# moister-v1_0.net
KiCad netlist of a schematic drawn in EAGLE
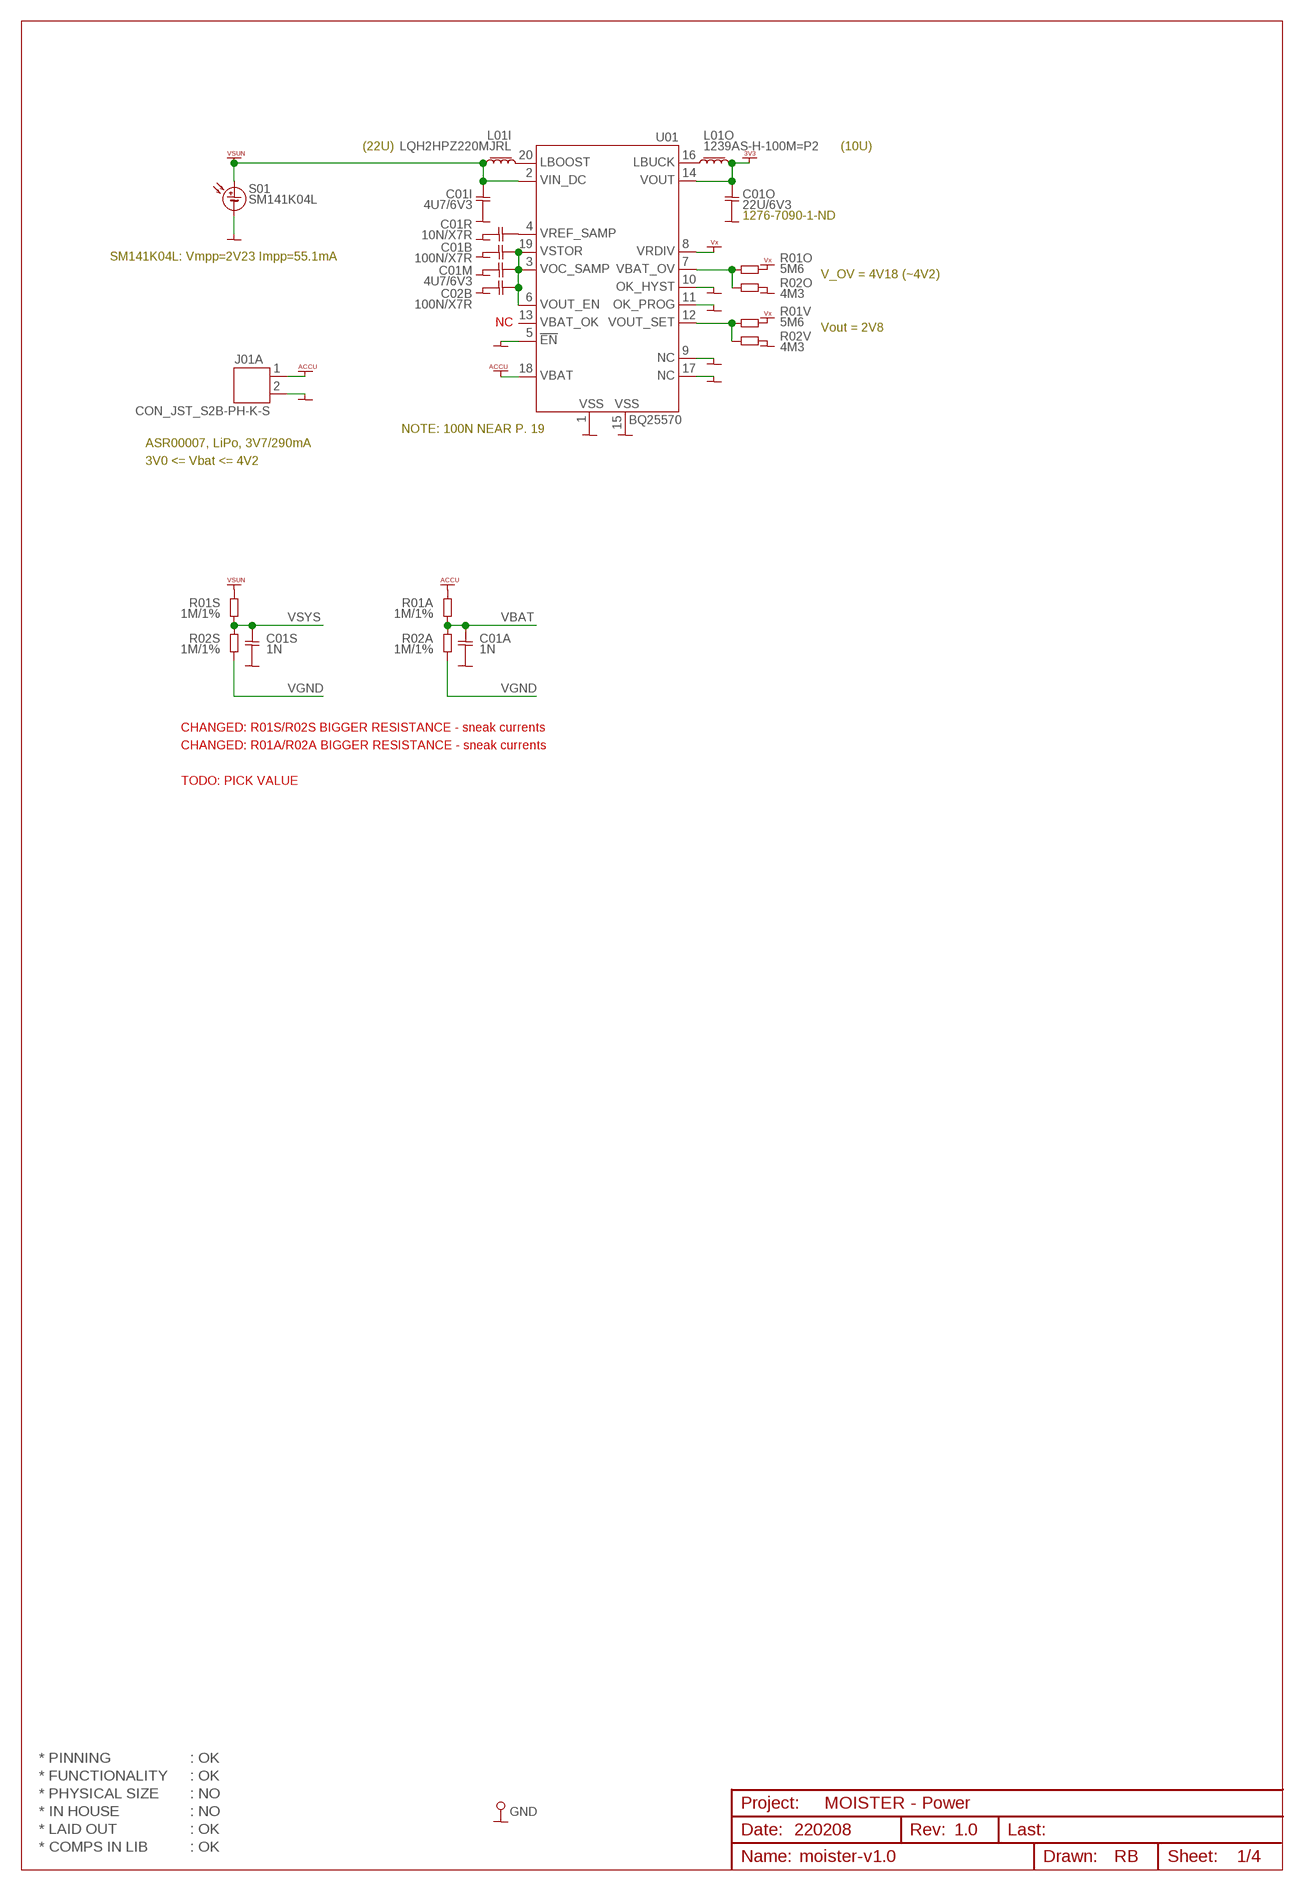
[diagram p0: schematic, sheet 1]
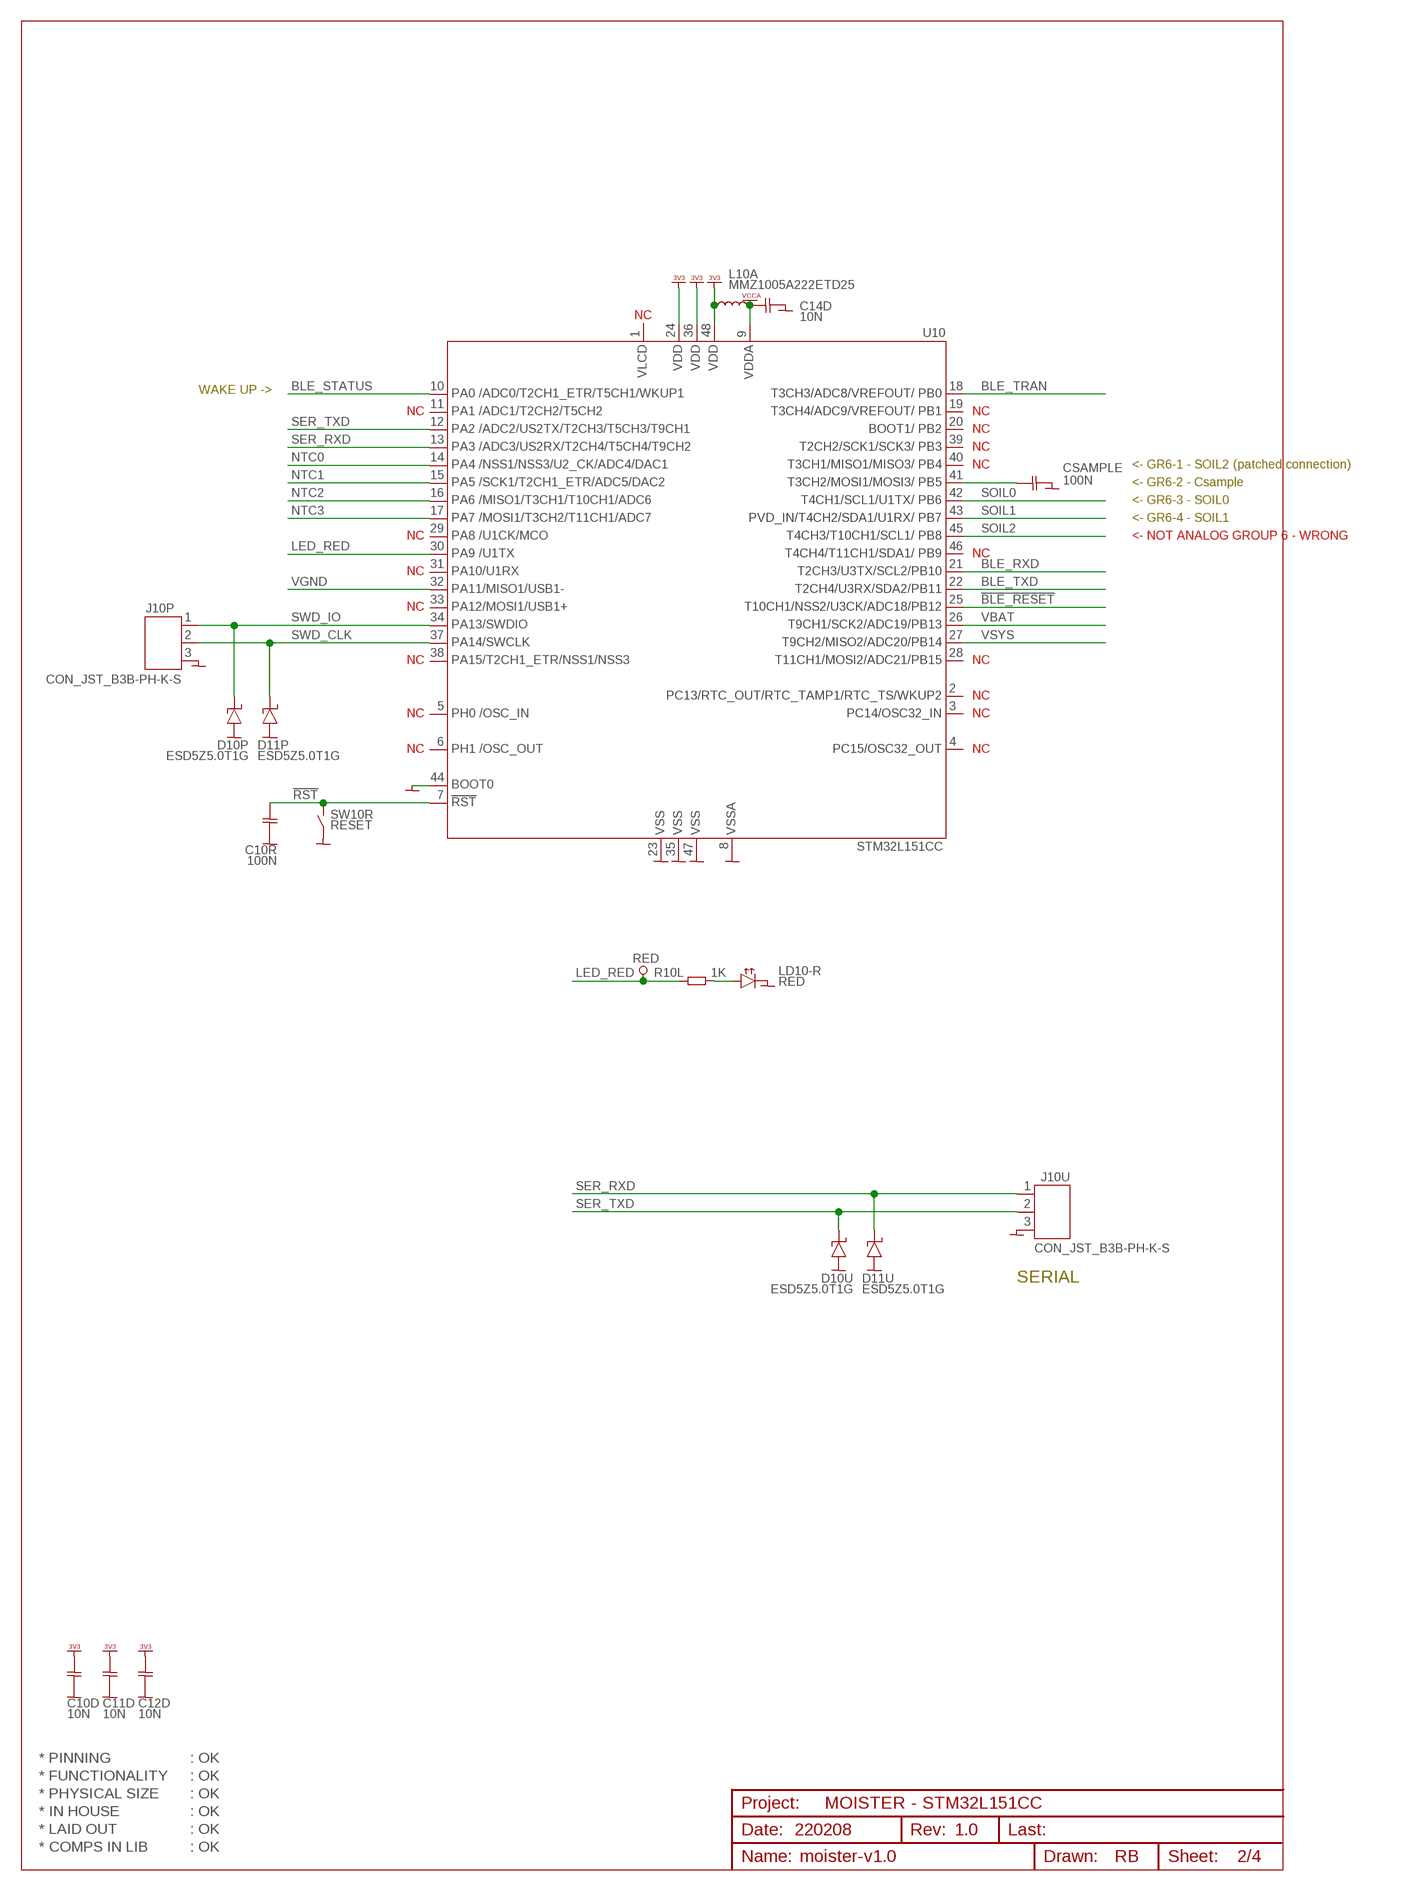
[diagram p1: schematic, sheet 2]
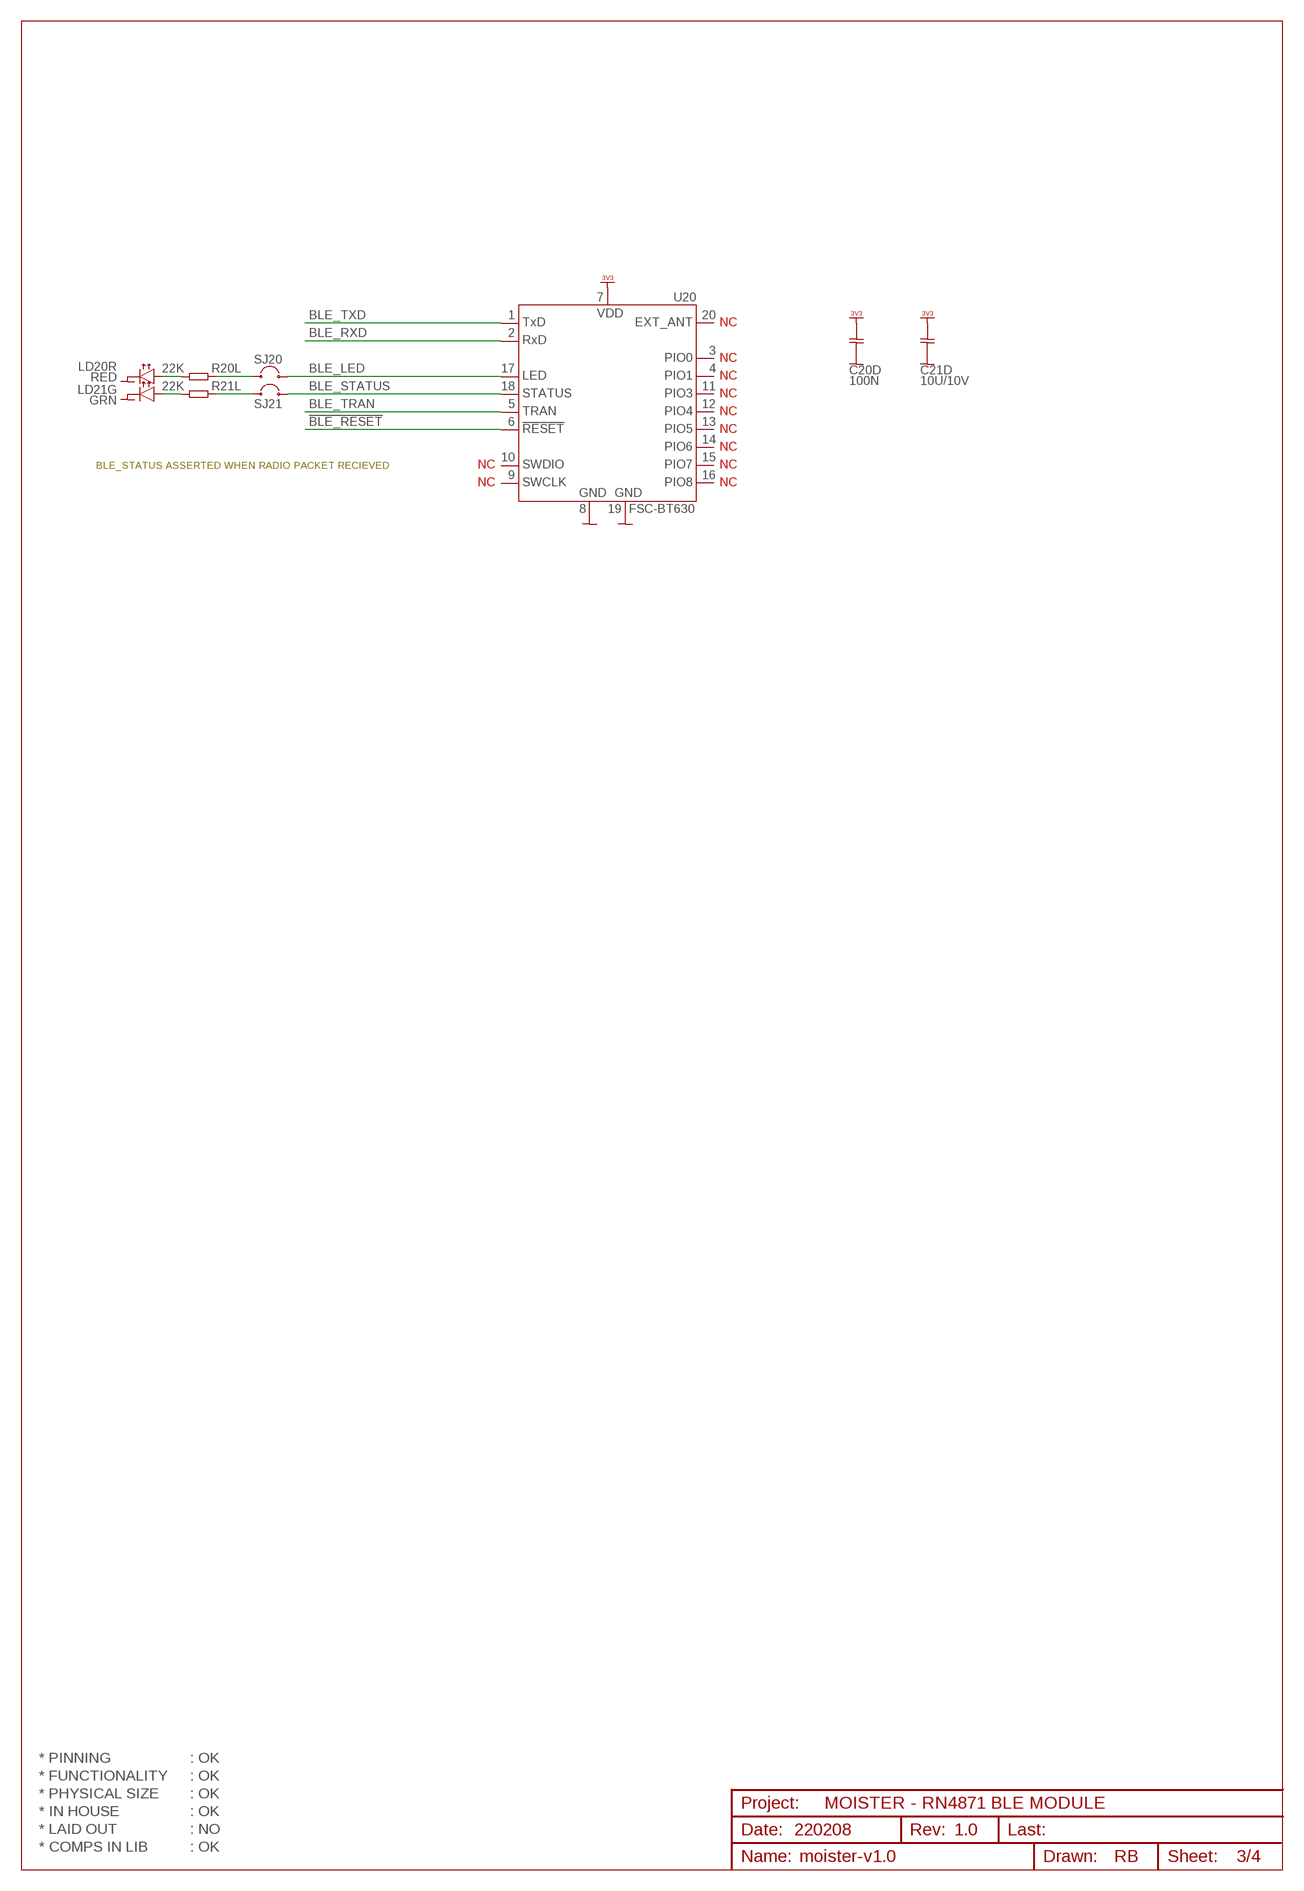
[diagram p2: schematic, sheet 3]
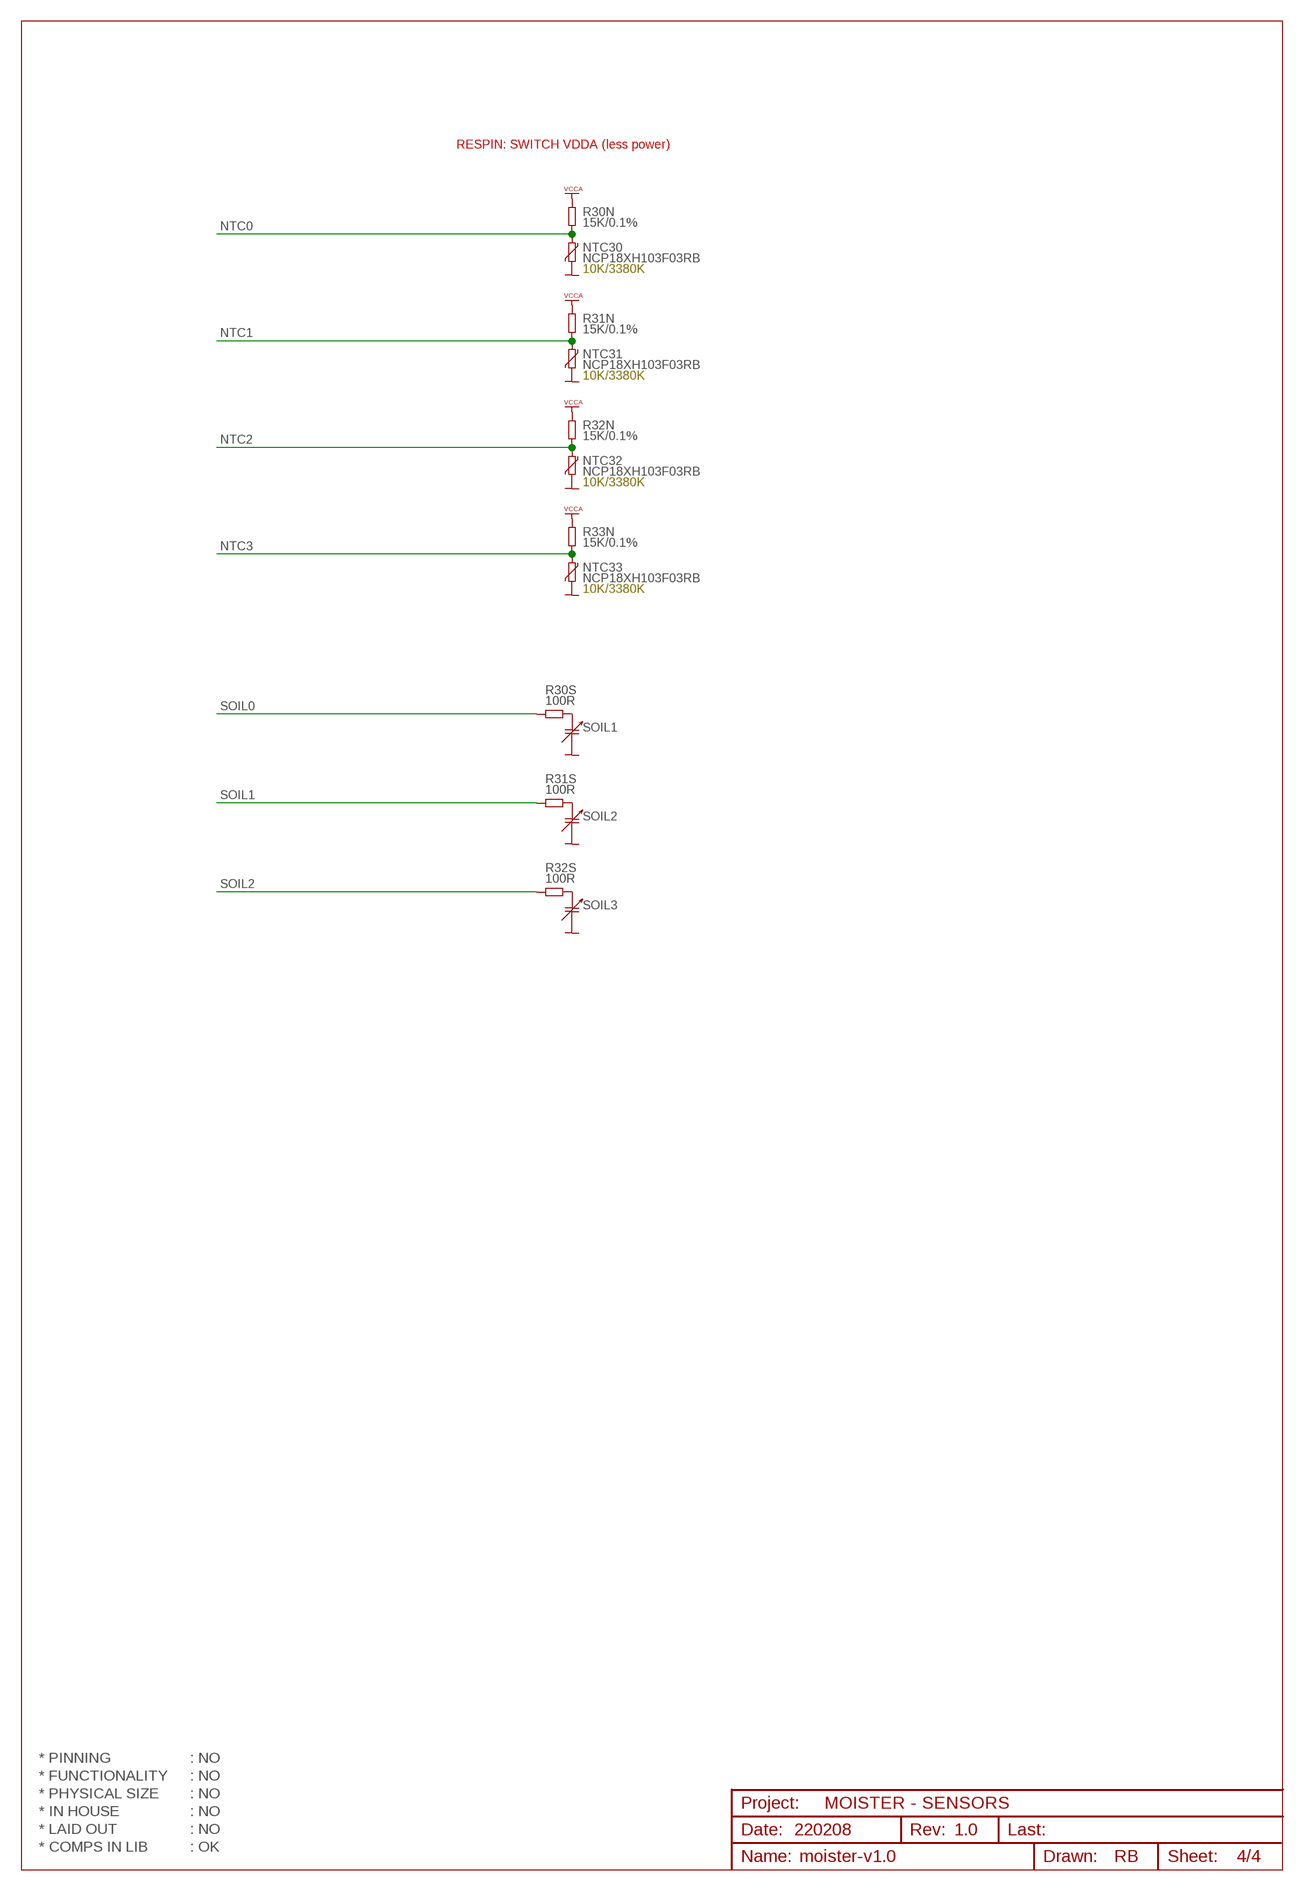
[diagram p3: schematic, sheet 4]

(export (version "E")
  (design (tool "Eeschema 10.0.6"))
  (components
    (comp (ref "C10D")
      (value "10N")
      (footprint "eagle-import:CAP0402")
      (libsource (lib "eagle-import") (part "CAP0402"))
    )
    (comp (ref "C10R")
      (value "100N")
      (footprint "eagle-import:CAP0402")
      (libsource (lib "eagle-import") (part "CAP0402"))
    )
    (comp (ref "C11D")
      (value "10N")
      (footprint "eagle-import:CAP0402")
      (libsource (lib "eagle-import") (part "CAP0402"))
    )
    (comp (ref "C12D")
      (value "10N")
      (footprint "eagle-import:CAP0402")
      (libsource (lib "eagle-import") (part "CAP0402"))
    )
    (comp (ref "C14D")
      (value "10N")
      (footprint "eagle-import:CAP0402")
      (libsource (lib "eagle-import") (part "CAP0402"))
    )
    (comp (ref "CSAMPLE")
      (value "100N")
      (footprint "eagle-import:CAP0603")
      (libsource (lib "eagle-import") (part "CAP0603"))
    )
    (comp (ref "D10P")
      (value "ESD5Z5.0T1G")
      (footprint "eagle-import:DIODE_SOD523")
      (libsource (lib "eagle-import") (part "DIODE_TVS_SOD523"))
    )
    (comp (ref "D10U")
      (value "ESD5Z5.0T1G")
      (footprint "eagle-import:DIODE_SOD523")
      (libsource (lib "eagle-import") (part "DIODE_TVS_SOD523"))
    )
    (comp (ref "D11P")
      (value "ESD5Z5.0T1G")
      (footprint "eagle-import:DIODE_SOD523")
      (libsource (lib "eagle-import") (part "DIODE_TVS_SOD523"))
    )
    (comp (ref "D11U")
      (value "ESD5Z5.0T1G")
      (footprint "eagle-import:DIODE_SOD523")
      (libsource (lib "eagle-import") (part "DIODE_TVS_SOD523"))
    )
    (comp (ref "J10P")
      (value "CON_JST_B3B-PH-K-S")
      (footprint "eagle-import:CON_JST_B3B-PH-K-S")
      (libsource (lib "eagle-import") (part "CON_JST_B3B-PH-K-S"))
    )
    (comp (ref "J10U")
      (value "CON_JST_B3B-PH-K-S")
      (footprint "eagle-import:CON_JST_B3B-PH-K-S")
      (libsource (lib "eagle-import") (part "CON_JST_B3B-PH-K-S"))
    )
    (comp (ref "L10A")
      (value "MMZ1005A222ETD25")
      (footprint "eagle-import:L_0402")
      (libsource (lib "eagle-import") (part "L_0402"))
    )
    (comp (ref "LD10-R")
      (value "RED")
      (footprint "eagle-import:LED_SMD_0402")
      (libsource (lib "eagle-import") (part "LED_SMD_0402"))
    )
    (comp (ref "R10L")
      (value "1K")
      (footprint "eagle-import:RES0402")
      (libsource (lib "eagle-import") (part "RES0402"))
    )
    (comp (ref "RED")
      (value "PIN_TEST_0.6MM")
      (footprint "eagle-import:HOLE_PTH_0.6MM")
      (libsource (lib "eagle-import") (part "PIN_TEST_0.6MM"))
    )
    (comp (ref "SW10R")
      (value "RESET")
      (footprint "eagle-import:SWITCH_SMD_PBUTTON_2P")
      (libsource (lib "eagle-import") (part "SWITCH_PUSHBUTTON"))
    )
    (comp (ref "U10")
      (value "STM32L151CC")
      (footprint "eagle-import:LQFP48")
      (libsource (lib "eagle-import") (part "STM32L151CC"))
    )
    (comp (ref "C20D")
      (value "100N")
      (footprint "eagle-import:CAP0402")
      (libsource (lib "eagle-import") (part "CAP0402"))
    )
    (comp (ref "C21D")
      (value "10U/10V")
      (footprint "eagle-import:CAP0402")
      (libsource (lib "eagle-import") (part "CAP0402"))
    )
    (comp (ref "LD20R")
      (value "RED")
      (footprint "eagle-import:LED_SMD_0402")
      (libsource (lib "eagle-import") (part "LED_SMD_0402"))
    )
    (comp (ref "LD21G")
      (value "GRN")
      (footprint "eagle-import:LED_SMD_0402")
      (libsource (lib "eagle-import") (part "LED_SMD_0402"))
    )
    (comp (ref "R20L")
      (value "22K")
      (footprint "eagle-import:RES0402")
      (libsource (lib "eagle-import") (part "RES0402"))
    )
    (comp (ref "R21L")
      (value "22K")
      (footprint "eagle-import:RES0402")
      (libsource (lib "eagle-import") (part "RES0402"))
    )
    (comp (ref "SJ20")
      (value "SJ2SJ2-S")
      (footprint "eagle-import:SJ2-S")
      (libsource (lib "eagle-import") (part "SJ2SJ2-S"))
    )
    (comp (ref "SJ21")
      (value "SJ2SJ2-S")
      (footprint "eagle-import:SJ2-S")
      (libsource (lib "eagle-import") (part "SJ2SJ2-S"))
    )
    (comp (ref "U20")
      (value "FSC-BT630")
      (footprint "eagle-import:FSC-BT630")
      (libsource (lib "eagle-import") (part "FSC-BT630"))
    )
    (comp (ref "NTC30")
      (value "NCP18XH103F03RB")
      (footprint "eagle-import:RES0603")
      (libsource (lib "eagle-import") (part "NTC0603"))
    )
    (comp (ref "NTC31")
      (value "NCP18XH103F03RB")
      (footprint "eagle-import:RES0603")
      (libsource (lib "eagle-import") (part "NTC0603"))
    )
    (comp (ref "NTC32")
      (value "NCP18XH103F03RB")
      (footprint "eagle-import:RES0603")
      (libsource (lib "eagle-import") (part "NTC0603"))
    )
    (comp (ref "NTC33")
      (value "NCP18XH103F03RB")
      (footprint "eagle-import:RES0603")
      (libsource (lib "eagle-import") (part "NTC0603"))
    )
    (comp (ref "R30N")
      (value "15K/0.1%")
      (footprint "eagle-import:RES0402")
      (libsource (lib "eagle-import") (part "RES0402"))
    )
    (comp (ref "R30S")
      (value "100R")
      (footprint "eagle-import:RES0402")
      (libsource (lib "eagle-import") (part "RES0402"))
    )
    (comp (ref "R31N")
      (value "15K/0.1%")
      (footprint "eagle-import:RES0402")
      (libsource (lib "eagle-import") (part "RES0402"))
    )
    (comp (ref "R31S")
      (value "100R")
      (footprint "eagle-import:RES0402")
      (libsource (lib "eagle-import") (part "RES0402"))
    )
    (comp (ref "R32N")
      (value "15K/0.1%")
      (footprint "eagle-import:RES0402")
      (libsource (lib "eagle-import") (part "RES0402"))
    )
    (comp (ref "R32S")
      (value "100R")
      (footprint "eagle-import:RES0402")
      (libsource (lib "eagle-import") (part "RES0402"))
    )
    (comp (ref "R33N")
      (value "15K/0.1%")
      (footprint "eagle-import:RES0402")
      (libsource (lib "eagle-import") (part "RES0402"))
    )
    (comp (ref "SOIL1")
      (value "CAP_SOIL_SINGLE_2LAYER")
      (footprint "eagle-import:CAP_SOIL_SINGLE_2LAYER")
      (libsource (lib "eagle-import") (part "CAP_SOIL_SINGLE_2LAYER"))
    )
    (comp (ref "SOIL2")
      (value "CAP_SOIL_SINGLE_2LAYER")
      (footprint "eagle-import:CAP_SOIL_SINGLE_2LAYER")
      (libsource (lib "eagle-import") (part "CAP_SOIL_SINGLE_2LAYER"))
    )
    (comp (ref "SOIL3")
      (value "CAP_SOIL_SINGLE_2LAYER")
      (footprint "eagle-import:CAP_SOIL_SINGLE_2LAYER")
      (libsource (lib "eagle-import") (part "CAP_SOIL_SINGLE_2LAYER"))
    )
    (comp (ref "C01A")
      (value "1N")
      (footprint "eagle-import:CAP0402")
      (libsource (lib "eagle-import") (part "CAP0402"))
    )
    (comp (ref "C01B")
      (value "100N/X7R")
      (footprint "eagle-import:CAP0402")
      (libsource (lib "eagle-import") (part "CAP0402"))
    )
    (comp (ref "C01I")
      (value "4U7/6V3")
      (footprint "eagle-import:CAP0402")
      (libsource (lib "eagle-import") (part "CAP0402"))
    )
    (comp (ref "C01M")
      (value "4U7/6V3")
      (footprint "eagle-import:CAP0402")
      (libsource (lib "eagle-import") (part "CAP0402"))
    )
    (comp (ref "C01O")
      (value "22U/6V3")
      (footprint "eagle-import:CAP0402")
      (libsource (lib "eagle-import") (part "CAP0402"))
    )
    (comp (ref "C01R")
      (value "10N/X7R")
      (footprint "eagle-import:CAP0402")
      (libsource (lib "eagle-import") (part "CAP0402"))
    )
    (comp (ref "C01S")
      (value "1N")
      (footprint "eagle-import:CAP0402")
      (libsource (lib "eagle-import") (part "CAP0402"))
    )
    (comp (ref "C02B")
      (value "100N/X7R")
      (footprint "eagle-import:CAP0402")
      (libsource (lib "eagle-import") (part "CAP0402"))
    )
    (comp (ref "GND")
      (value "PIN_TEST")
      (footprint "eagle-import:HOLE_PTH_0.8MM")
      (libsource (lib "eagle-import") (part "PIN_TEST"))
    )
    (comp (ref "J01A")
      (value "CON_JST_S2B-PH-K-S")
      (footprint "eagle-import:CON_JST_S2B-PH-K-S")
      (libsource (lib "eagle-import") (part "CON_JST_S2B-PH-K-S"))
    )
    (comp (ref "L01I")
      (value "LQH2HPZ220MJRL")
      (footprint "eagle-import:L_1008")
      (libsource (lib "eagle-import") (part "L_1008"))
    )
    (comp (ref "L01O")
      (value "1239AS-H-100M=P2")
      (footprint "eagle-import:L_1008")
      (libsource (lib "eagle-import") (part "L_1008"))
    )
    (comp (ref "R01A")
      (value "1M/1%")
      (footprint "eagle-import:RES0402")
      (libsource (lib "eagle-import") (part "RES0402"))
    )
    (comp (ref "R01O")
      (value "5M6")
      (footprint "eagle-import:RES0402")
      (libsource (lib "eagle-import") (part "RES0402"))
    )
    (comp (ref "R01S")
      (value "1M/1%")
      (footprint "eagle-import:RES0402")
      (libsource (lib "eagle-import") (part "RES0402"))
    )
    (comp (ref "R01V")
      (value "5M6")
      (footprint "eagle-import:RES0402")
      (libsource (lib "eagle-import") (part "RES0402"))
    )
    (comp (ref "R02A")
      (value "1M/1%")
      (footprint "eagle-import:RES0402")
      (libsource (lib "eagle-import") (part "RES0402"))
    )
    (comp (ref "R02O")
      (value "4M3")
      (footprint "eagle-import:RES0402")
      (libsource (lib "eagle-import") (part "RES0402"))
    )
    (comp (ref "R02S")
      (value "1M/1%")
      (footprint "eagle-import:RES0402")
      (libsource (lib "eagle-import") (part "RES0402"))
    )
    (comp (ref "R02V")
      (value "4M3")
      (footprint "eagle-import:RES0402")
      (libsource (lib "eagle-import") (part "RES0402"))
    )
    (comp (ref "S01")
      (value "SM141K04L")
      (footprint "eagle-import:SM141K04L")
      (libsource (lib "eagle-import") (part "SM141K04L"))
    )
    (comp (ref "U01")
      (value "BQ25570")
      (footprint "eagle-import:VQFN20")
      (libsource (lib "eagle-import") (part "BQ25570"))
    )
  )
  (nets
    (net (code "1") (name "ACCU") (class "Default")
      (node (ref "J01A") (pin "1") (pinfunction "1_1") (pintype "passive"))
      (node (ref "R01A") (pin "2") (pinfunction "2_2") (pintype "passive"))
      (node (ref "U01") (pin "18") (pinfunction "18.VBAT_18") (pintype "passive"))
    )
    (net (code "2") (name "BLE_LED") (class "Default")
      (node (ref "SJ20") (pin "2") (pinfunction "P$2_2") (pintype "passive"))
      (node (ref "U20") (pin "17") (pinfunction "17.LED_17") (pintype "passive"))
    )
    (net (code "3") (name "BLE_RXD") (class "Default")
      (node (ref "U10") (pin "21") (pinfunction "21.PB10_21") (pintype "passive"))
      (node (ref "U20") (pin "2") (pinfunction "2.RXD_2") (pintype "passive"))
    )
    (net (code "4") (name "BLE_STATUS") (class "Default")
      (node (ref "SJ21") (pin "2") (pinfunction "P$2_2") (pintype "passive"))
      (node (ref "U10") (pin "10") (pinfunction "10.PA0_10") (pintype "passive"))
      (node (ref "U20") (pin "18") (pinfunction "18.STATUS_18") (pintype "passive"))
    )
    (net (code "5") (name "BLE_TRAN") (class "Default")
      (node (ref "U10") (pin "18") (pinfunction "18.PB0_18") (pintype "passive"))
      (node (ref "U20") (pin "5") (pinfunction "5.TRAN_5") (pintype "passive"))
    )
    (net (code "6") (name "BLE_TXD") (class "Default")
      (node (ref "U10") (pin "22") (pinfunction "22.PB11_22") (pintype "passive"))
      (node (ref "U20") (pin "1") (pinfunction "1.TXD_1") (pintype "passive"))
    )
    (net (code "7") (name "GND") (class "Default")
      (node (ref "C01A") (pin "2") (pinfunction "2_2") (pintype "passive"))
      (node (ref "C01B") (pin "2") (pinfunction "2_2") (pintype "passive"))
      (node (ref "C01I") (pin "2") (pinfunction "2_2") (pintype "passive"))
      (node (ref "C01M") (pin "2") (pinfunction "2_2") (pintype "passive"))
      (node (ref "C01O") (pin "2") (pinfunction "2_2") (pintype "passive"))
      (node (ref "C01R") (pin "2") (pinfunction "2_2") (pintype "passive"))
      (node (ref "C01S") (pin "2") (pinfunction "2_2") (pintype "passive"))
      (node (ref "C02B") (pin "2") (pinfunction "2_2") (pintype "passive"))
      (node (ref "C10D") (pin "2") (pinfunction "2_2") (pintype "passive"))
      (node (ref "C10R") (pin "2") (pinfunction "2_2") (pintype "passive"))
      (node (ref "C11D") (pin "2") (pinfunction "2_2") (pintype "passive"))
      (node (ref "C12D") (pin "2") (pinfunction "2_2") (pintype "passive"))
      (node (ref "C14D") (pin "2") (pinfunction "2_2") (pintype "passive"))
      (node (ref "C20D") (pin "2") (pinfunction "2_2") (pintype "passive"))
      (node (ref "C21D") (pin "2") (pinfunction "2_2") (pintype "passive"))
      (node (ref "CSAMPLE") (pin "2") (pinfunction "2_2") (pintype "passive"))
      (node (ref "D10P") (pin "A") (pinfunction "A_A") (pintype "passive"))
      (node (ref "D10U") (pin "A") (pinfunction "A_A") (pintype "passive"))
      (node (ref "D11P") (pin "A") (pinfunction "A_A") (pintype "passive"))
      (node (ref "D11U") (pin "A") (pinfunction "A_A") (pintype "passive"))
      (node (ref "GND") (pin "1") (pinfunction "P$1_1") (pintype "passive"))
      (node (ref "J01A") (pin "2") (pinfunction "2_2") (pintype "passive"))
      (node (ref "J10P") (pin "3") (pinfunction "3_3") (pintype "passive"))
      (node (ref "J10U") (pin "3") (pinfunction "3_3") (pintype "passive"))
      (node (ref "LD10-R") (pin "C") (pinfunction "C_C") (pintype "passive"))
      (node (ref "LD20R") (pin "C") (pinfunction "C_C") (pintype "passive"))
      (node (ref "LD21G") (pin "C") (pinfunction "C_C") (pintype "passive"))
      (node (ref "NTC30") (pin "1") (pinfunction "P$1_1") (pintype "passive"))
      (node (ref "NTC31") (pin "1") (pinfunction "P$1_1") (pintype "passive"))
      (node (ref "NTC32") (pin "1") (pinfunction "P$1_1") (pintype "passive"))
      (node (ref "NTC33") (pin "1") (pinfunction "P$1_1") (pintype "passive"))
      (node (ref "R02O") (pin "2") (pinfunction "2_2") (pintype "passive"))
      (node (ref "R02V") (pin "2") (pinfunction "2_2") (pintype "passive"))
      (node (ref "S01") (pin "-") (pinfunction "-_-") (pintype "passive"))
      (node (ref "SOIL1") (pin "2") (pinfunction "2_2") (pintype "passive"))
      (node (ref "SOIL2") (pin "2") (pinfunction "2_2") (pintype "passive"))
      (node (ref "SOIL3") (pin "2") (pinfunction "2_2") (pintype "passive"))
      (node (ref "SW10R") (pin "2") (pinfunction "3-4_2") (pintype "passive"))
      (node (ref "U01") (pin "1") (pinfunction "1.VSS_1") (pintype "passive"))
      (node (ref "U01") (pin "10") (pinfunction "10.OK_HYST_10") (pintype "passive"))
      (node (ref "U01") (pin "11") (pinfunction "11.OK_PROG_11") (pintype "passive"))
      (node (ref "U01") (pin "15") (pinfunction "15.VSS_15") (pintype "passive"))
      (node (ref "U01") (pin "17") (pinfunction "17.NC_17") (pintype "passive"))
      (node (ref "U01") (pin "5") (pinfunction "5.~{EN}_5") (pintype "passive"))
      (node (ref "U01") (pin "9") (pinfunction "9.NC_9") (pintype "passive"))
      (node (ref "U01") (pin "TP") (pinfunction "15.VSS_TP") (pintype "passive"))
      (node (ref "U01") (pin "V1") (pinfunction "15.VSS_V1") (pintype "passive"))
      (node (ref "U01") (pin "V2") (pinfunction "15.VSS_V2") (pintype "passive"))
      (node (ref "U01") (pin "V3") (pinfunction "15.VSS_V3") (pintype "passive"))
      (node (ref "U01") (pin "V4") (pinfunction "15.VSS_V4") (pintype "passive"))
      (node (ref "U10") (pin "23") (pinfunction "23.GND_23") (pintype "passive"))
      (node (ref "U10") (pin "35") (pinfunction "35.GND_35") (pintype "passive"))
      (node (ref "U10") (pin "44") (pinfunction "44.BOOT0_44") (pintype "passive"))
      (node (ref "U10") (pin "47") (pinfunction "47.GND_47") (pintype "passive"))
      (node (ref "U10") (pin "8") (pinfunction "8.GND_8") (pintype "passive"))
      (node (ref "U20") (pin "19") (pinfunction "19.GND_19") (pintype "passive"))
      (node (ref "U20") (pin "8") (pinfunction "8.GND_8") (pintype "passive"))
    )
    (net (code "8") (name "LED_RED") (class "Default")
      (node (ref "R10L") (pin "1") (pinfunction "1_1") (pintype "passive"))
      (node (ref "RED") (pin "1") (pinfunction "P$1_1") (pintype "passive"))
      (node (ref "U10") (pin "30") (pinfunction "30.PA9_30") (pintype "passive"))
    )
    (net (code "9") (name "NTC0") (class "Default")
      (node (ref "NTC30") (pin "2") (pinfunction "P$2_2") (pintype "passive"))
      (node (ref "R30N") (pin "2") (pinfunction "2_2") (pintype "passive"))
      (node (ref "U10") (pin "14") (pinfunction "14.PA4_14") (pintype "passive"))
    )
    (net (code "10") (name "NTC1") (class "Default")
      (node (ref "NTC31") (pin "2") (pinfunction "P$2_2") (pintype "passive"))
      (node (ref "R31N") (pin "2") (pinfunction "2_2") (pintype "passive"))
      (node (ref "U10") (pin "15") (pinfunction "15.PA5_15") (pintype "passive"))
    )
    (net (code "11") (name "NTC2") (class "Default")
      (node (ref "NTC32") (pin "2") (pinfunction "P$2_2") (pintype "passive"))
      (node (ref "R32N") (pin "2") (pinfunction "2_2") (pintype "passive"))
      (node (ref "U10") (pin "16") (pinfunction "16.PA6_16") (pintype "passive"))
    )
    (net (code "12") (name "NTC3") (class "Default")
      (node (ref "NTC33") (pin "2") (pinfunction "P$2_2") (pintype "passive"))
      (node (ref "R33N") (pin "2") (pinfunction "2_2") (pintype "passive"))
      (node (ref "U10") (pin "17") (pinfunction "17.PA7_17") (pintype "passive"))
    )
    (net (code "13") (name "Net-(LD10-R-PadA)") (class "Default")
      (node (ref "LD10-R") (pin "A") (pinfunction "A_A") (pintype "passive"))
      (node (ref "R10L") (pin "2") (pinfunction "2_2") (pintype "passive"))
    )
    (net (code "14") (name "Net-(LD20R-PadA)") (class "Default")
      (node (ref "LD20R") (pin "A") (pinfunction "A_A") (pintype "passive"))
      (node (ref "R20L") (pin "2") (pinfunction "2_2") (pintype "passive"))
    )
    (net (code "15") (name "Net-(LD21G-PadA)") (class "Default")
      (node (ref "LD21G") (pin "A") (pinfunction "A_A") (pintype "passive"))
      (node (ref "R21L") (pin "2") (pinfunction "2_2") (pintype "passive"))
    )
    (net (code "16") (name "Net-(R30S-Pad2)") (class "Default")
      (node (ref "R30S") (pin "2") (pinfunction "2_2") (pintype "passive"))
      (node (ref "SOIL1") (pin "1") (pinfunction "1_1") (pintype "passive"))
    )
    (net (code "17") (name "Net-(R31S-Pad2)") (class "Default")
      (node (ref "R31S") (pin "2") (pinfunction "2_2") (pintype "passive"))
      (node (ref "SOIL2") (pin "1") (pinfunction "1_1") (pintype "passive"))
    )
    (net (code "18") (name "Net-(R32S-Pad2)") (class "Default")
      (node (ref "R32S") (pin "2") (pinfunction "2_2") (pintype "passive"))
      (node (ref "SOIL3") (pin "1") (pinfunction "1_1") (pintype "passive"))
    )
    (net (code "19") (name "Net-(SJ20-P$1)") (class "Default")
      (node (ref "R20L") (pin "1") (pinfunction "1_1") (pintype "passive"))
      (node (ref "SJ20") (pin "1") (pinfunction "P$1_1") (pintype "passive"))
    )
    (net (code "20") (name "Net-(SJ21-P$1)") (class "Default")
      (node (ref "R21L") (pin "1") (pinfunction "1_1") (pintype "passive"))
      (node (ref "SJ21") (pin "1") (pinfunction "P$1_1") (pintype "passive"))
    )
    (net (code "21") (name "Net-(U01-4.VREF_SAMP)") (class "Default")
      (node (ref "C01R") (pin "1") (pinfunction "1_1") (pintype "passive"))
      (node (ref "U01") (pin "4") (pinfunction "4.VREF_SAMP_4") (pintype "passive"))
    )
    (net (code "22") (name "Net-(U01-7.VBAT_OV)") (class "Default")
      (node (ref "R01O") (pin "2") (pinfunction "2_2") (pintype "passive"))
      (node (ref "R02O") (pin "1") (pinfunction "1_1") (pintype "passive"))
      (node (ref "U01") (pin "7") (pinfunction "7.VBAT_OV_7") (pintype "passive"))
    )
    (net (code "23") (name "Net-(U01-12.VOUT_SET)") (class "Default")
      (node (ref "R01V") (pin "2") (pinfunction "2_2") (pintype "passive"))
      (node (ref "R02V") (pin "1") (pinfunction "1_1") (pintype "passive"))
      (node (ref "U01") (pin "12") (pinfunction "12.VOUT_SET_12") (pintype "passive"))
    )
    (net (code "24") (name "Net-(U01-16.LBUCK)") (class "Default")
      (node (ref "L01O") (pin "1") (pinfunction "1_1") (pintype "passive"))
      (node (ref "U01") (pin "16") (pinfunction "16.LBUCK_16") (pintype "passive"))
    )
    (net (code "25") (name "Net-(U01-19.VSTOR)") (class "Default")
      (node (ref "C01B") (pin "1") (pinfunction "1_1") (pintype "passive"))
      (node (ref "C01M") (pin "1") (pinfunction "1_1") (pintype "passive"))
      (node (ref "C02B") (pin "1") (pinfunction "1_1") (pintype "passive"))
      (node (ref "U01") (pin "19") (pinfunction "19.VSTOR_19") (pintype "passive"))
      (node (ref "U01") (pin "3") (pinfunction "3.VOC_SAMP_3") (pintype "passive"))
      (node (ref "U01") (pin "6") (pinfunction "6.VOUT_EN_6") (pintype "passive"))
    )
    (net (code "26") (name "Net-(U01-20.LBOOST)") (class "Default")
      (node (ref "L01I") (pin "2") (pinfunction "2_2") (pintype "passive"))
      (node (ref "U01") (pin "20") (pinfunction "20.LBOOST_20") (pintype "passive"))
    )
    (net (code "27") (name "Net-(U10-41.PB5)") (class "Default")
      (node (ref "CSAMPLE") (pin "1") (pinfunction "1_1") (pintype "passive"))
      (node (ref "U10") (pin "41") (pinfunction "41.PB5_41") (pintype "passive"))
    )
    (net (code "28") (name "SER_RXD") (class "Default")
      (node (ref "D11U") (pin "C") (pinfunction "C_C") (pintype "passive"))
      (node (ref "J10U") (pin "1") (pinfunction "1_1") (pintype "passive"))
      (node (ref "U10") (pin "13") (pinfunction "13.PA3_13") (pintype "passive"))
    )
    (net (code "29") (name "SER_TXD") (class "Default")
      (node (ref "D10U") (pin "C") (pinfunction "C_C") (pintype "passive"))
      (node (ref "J10U") (pin "2") (pinfunction "2_2") (pintype "passive"))
      (node (ref "U10") (pin "12") (pinfunction "12.PA2_12") (pintype "passive"))
    )
    (net (code "30") (name "SOIL0") (class "Default")
      (node (ref "R30S") (pin "1") (pinfunction "1_1") (pintype "passive"))
      (node (ref "U10") (pin "42") (pinfunction "42.PB6_42") (pintype "passive"))
    )
    (net (code "31") (name "SOIL1") (class "Default")
      (node (ref "R31S") (pin "1") (pinfunction "1_1") (pintype "passive"))
      (node (ref "U10") (pin "43") (pinfunction "43.PB7_43") (pintype "passive"))
    )
    (net (code "32") (name "SOIL2") (class "Default")
      (node (ref "R32S") (pin "1") (pinfunction "1_1") (pintype "passive"))
      (node (ref "U10") (pin "45") (pinfunction "45.PB8_45") (pintype "passive"))
    )
    (net (code "33") (name "SWD_CLK") (class "Default")
      (node (ref "D11P") (pin "C") (pinfunction "C_C") (pintype "passive"))
      (node (ref "J10P") (pin "2") (pinfunction "2_2") (pintype "passive"))
      (node (ref "U10") (pin "37") (pinfunction "37.PA14_37") (pintype "passive"))
    )
    (net (code "34") (name "SWD_IO") (class "Default")
      (node (ref "D10P") (pin "C") (pinfunction "C_C") (pintype "passive"))
      (node (ref "J10P") (pin "1") (pinfunction "1_1") (pintype "passive"))
      (node (ref "U10") (pin "34") (pinfunction "34.PA13_34") (pintype "passive"))
    )
    (net (code "35") (name "VBAT") (class "Default")
      (node (ref "C01A") (pin "1") (pinfunction "1_1") (pintype "passive"))
      (node (ref "R01A") (pin "1") (pinfunction "1_1") (pintype "passive"))
      (node (ref "R02A") (pin "2") (pinfunction "2_2") (pintype "passive"))
      (node (ref "U10") (pin "26") (pinfunction "26.PB13_26") (pintype "passive"))
    )
    (net (code "36") (name "VCCA") (class "Default")
      (node (ref "C14D") (pin "1") (pinfunction "1_1") (pintype "passive"))
      (node (ref "L10A") (pin "2") (pinfunction "2_2") (pintype "passive"))
      (node (ref "R30N") (pin "1") (pinfunction "1_1") (pintype "passive"))
      (node (ref "R31N") (pin "1") (pinfunction "1_1") (pintype "passive"))
      (node (ref "R32N") (pin "1") (pinfunction "1_1") (pintype "passive"))
      (node (ref "R33N") (pin "1") (pinfunction "1_1") (pintype "passive"))
      (node (ref "U10") (pin "9") (pinfunction "9.VDD_9") (pintype "passive"))
    )
    (net (code "37") (name "VDD_3V3") (class "Default")
      (node (ref "C01O") (pin "1") (pinfunction "1_1") (pintype "passive"))
      (node (ref "C10D") (pin "1") (pinfunction "1_1") (pintype "passive"))
      (node (ref "C11D") (pin "1") (pinfunction "1_1") (pintype "passive"))
      (node (ref "C12D") (pin "1") (pinfunction "1_1") (pintype "passive"))
      (node (ref "C20D") (pin "1") (pinfunction "1_1") (pintype "passive"))
      (node (ref "C21D") (pin "1") (pinfunction "1_1") (pintype "passive"))
      (node (ref "L01O") (pin "2") (pinfunction "2_2") (pintype "passive"))
      (node (ref "L10A") (pin "1") (pinfunction "1_1") (pintype "passive"))
      (node (ref "U01") (pin "14") (pinfunction "14.VOUT_14") (pintype "passive"))
      (node (ref "U10") (pin "24") (pinfunction "24.VDD_24") (pintype "passive"))
      (node (ref "U10") (pin "36") (pinfunction "36.VDD_36") (pintype "passive"))
      (node (ref "U10") (pin "48") (pinfunction "48.VDD_48") (pintype "passive"))
      (node (ref "U20") (pin "7") (pinfunction "7.VDD_7") (pintype "passive"))
    )
    (net (code "38") (name "VGND") (class "Default")
      (node (ref "R02A") (pin "1") (pinfunction "1_1") (pintype "passive"))
      (node (ref "R02S") (pin "1") (pinfunction "1_1") (pintype "passive"))
      (node (ref "U10") (pin "32") (pinfunction "32.PA11_32") (pintype "passive"))
    )
    (net (code "39") (name "VSUN") (class "Default")
      (node (ref "C01I") (pin "1") (pinfunction "1_1") (pintype "passive"))
      (node (ref "L01I") (pin "1") (pinfunction "1_1") (pintype "passive"))
      (node (ref "R01S") (pin "2") (pinfunction "2_2") (pintype "passive"))
      (node (ref "S01") (pin "+") (pinfunction "+_+") (pintype "passive"))
      (node (ref "U01") (pin "2") (pinfunction "2.VIN_DC_2") (pintype "passive"))
    )
    (net (code "40") (name "VSYS") (class "Default")
      (node (ref "C01S") (pin "1") (pinfunction "1_1") (pintype "passive"))
      (node (ref "R01S") (pin "1") (pinfunction "1_1") (pintype "passive"))
      (node (ref "R02S") (pin "2") (pinfunction "2_2") (pintype "passive"))
      (node (ref "U10") (pin "27") (pinfunction "27.PB14_27") (pintype "passive"))
    )
    (net (code "41") (name "VX") (class "Default")
      (node (ref "R01O") (pin "1") (pinfunction "1_1") (pintype "passive"))
      (node (ref "R01V") (pin "1") (pinfunction "1_1") (pintype "passive"))
      (node (ref "U01") (pin "8") (pinfunction "8.VRDIV_8") (pintype "passive"))
    )
    (net (code "42") (name "unconnected-(U01-13.VBAT_OK-Pad13)") (class "Default")
      (node (ref "U01") (pin "13") (pinfunction "13.VBAT_OK_13") (pintype "passive"))
    )
    (net (code "43") (name "unconnected-(U10-1.VDD-Pad1)") (class "Default")
      (node (ref "U10") (pin "1") (pinfunction "1.VDD_1") (pintype "passive"))
    )
    (net (code "44") (name "unconnected-(U10-2.PC13-Pad2)") (class "Default")
      (node (ref "U10") (pin "2") (pinfunction "2.PC13_2") (pintype "passive"))
    )
    (net (code "45") (name "unconnected-(U10-3.PC14-Pad3)") (class "Default")
      (node (ref "U10") (pin "3") (pinfunction "3.PC14_3") (pintype "passive"))
    )
    (net (code "46") (name "unconnected-(U10-4.PC15-Pad4)") (class "Default")
      (node (ref "U10") (pin "4") (pinfunction "4.PC15_4") (pintype "passive"))
    )
    (net (code "47") (name "unconnected-(U10-5.OSC_IN-Pad5)") (class "Default")
      (node (ref "U10") (pin "5") (pinfunction "5.OSC_IN_5") (pintype "passive"))
    )
    (net (code "48") (name "unconnected-(U10-6.OSC_OUT-Pad6)") (class "Default")
      (node (ref "U10") (pin "6") (pinfunction "6.OSC_OUT_6") (pintype "passive"))
    )
    (net (code "49") (name "unconnected-(U10-11.PA1-Pad11)") (class "Default")
      (node (ref "U10") (pin "11") (pinfunction "11.PA1_11") (pintype "passive"))
    )
    (net (code "50") (name "unconnected-(U10-19.PB1-Pad19)") (class "Default")
      (node (ref "U10") (pin "19") (pinfunction "19.PB1_19") (pintype "passive"))
    )
    (net (code "51") (name "unconnected-(U10-20.PB2-Pad20)") (class "Default")
      (node (ref "U10") (pin "20") (pinfunction "20.PB2_20") (pintype "passive"))
    )
    (net (code "52") (name "unconnected-(U10-28.PB15-Pad28)") (class "Default")
      (node (ref "U10") (pin "28") (pinfunction "28.PB15_28") (pintype "passive"))
    )
    (net (code "53") (name "unconnected-(U10-29.PA8-Pad29)") (class "Default")
      (node (ref "U10") (pin "29") (pinfunction "29.PA8_29") (pintype "passive"))
    )
    (net (code "54") (name "unconnected-(U10-31.PA10-Pad31)") (class "Default")
      (node (ref "U10") (pin "31") (pinfunction "31.PA10_31") (pintype "passive"))
    )
    (net (code "55") (name "unconnected-(U10-33.PA12-Pad33)") (class "Default")
      (node (ref "U10") (pin "33") (pinfunction "33.PA12_33") (pintype "passive"))
    )
    (net (code "56") (name "unconnected-(U10-38.PA15-Pad38)") (class "Default")
      (node (ref "U10") (pin "38") (pinfunction "38.PA15_38") (pintype "passive"))
    )
    (net (code "57") (name "unconnected-(U10-39.PB3-Pad39)") (class "Default")
      (node (ref "U10") (pin "39") (pinfunction "39.PB3_39") (pintype "passive"))
    )
    (net (code "58") (name "unconnected-(U10-40.PB4-Pad40)") (class "Default")
      (node (ref "U10") (pin "40") (pinfunction "40.PB4_40") (pintype "passive"))
    )
    (net (code "59") (name "unconnected-(U10-46.PB9-Pad46)") (class "Default")
      (node (ref "U10") (pin "46") (pinfunction "46.PB9_46") (pintype "passive"))
    )
    (net (code "60") (name "unconnected-(U20-3.PIO0-Pad3)") (class "Default")
      (node (ref "U20") (pin "3") (pinfunction "3.PIO0_3") (pintype "passive"))
    )
    (net (code "61") (name "unconnected-(U20-4.PIO1-Pad4)") (class "Default")
      (node (ref "U20") (pin "4") (pinfunction "4.PIO1_4") (pintype "passive"))
    )
    (net (code "62") (name "unconnected-(U20-9.SWCLK-Pad9)") (class "Default")
      (node (ref "U20") (pin "9") (pinfunction "9.SWCLK_9") (pintype "passive"))
    )
    (net (code "63") (name "unconnected-(U20-10.SWDIO-Pad10)") (class "Default")
      (node (ref "U20") (pin "10") (pinfunction "10.SWDIO_10") (pintype "passive"))
    )
    (net (code "64") (name "unconnected-(U20-11.PIO3-Pad11)") (class "Default")
      (node (ref "U20") (pin "11") (pinfunction "11.PIO3_11") (pintype "passive"))
    )
    (net (code "65") (name "unconnected-(U20-12.PIO4-Pad12)") (class "Default")
      (node (ref "U20") (pin "12") (pinfunction "12.PIO4_12") (pintype "passive"))
    )
    (net (code "66") (name "unconnected-(U20-13.PIO5-Pad13)") (class "Default")
      (node (ref "U20") (pin "13") (pinfunction "13.PIO5_13") (pintype "passive"))
    )
    (net (code "67") (name "unconnected-(U20-14.PIO6-Pad14)") (class "Default")
      (node (ref "U20") (pin "14") (pinfunction "14.PIO6_14") (pintype "passive"))
    )
    (net (code "68") (name "unconnected-(U20-15.PIO7-Pad15)") (class "Default")
      (node (ref "U20") (pin "15") (pinfunction "15.PIO7_15") (pintype "passive"))
    )
    (net (code "69") (name "unconnected-(U20-16.PIO8-Pad16)") (class "Default")
      (node (ref "U20") (pin "16") (pinfunction "16.PIO8_16") (pintype "passive"))
    )
    (net (code "70") (name "unconnected-(U20-20.EXT_ANT-Pad20)") (class "Default")
      (node (ref "U20") (pin "20") (pinfunction "20.EXT_ANT_20") (pintype "passive"))
    )
    (net (code "71") (name "~{BLE_RESET}") (class "Default")
      (node (ref "U10") (pin "25") (pinfunction "25.PB12_25") (pintype "passive"))
      (node (ref "U20") (pin "6") (pinfunction "6.~{RESET}_6") (pintype "passive"))
    )
    (net (code "72") (name "~{RST}") (class "Default")
      (node (ref "C10R") (pin "1") (pinfunction "1_1") (pintype "passive"))
      (node (ref "SW10R") (pin "1") (pinfunction "1-2_1") (pintype "passive"))
      (node (ref "U10") (pin "7") (pinfunction "7.~{RST}_7") (pintype "passive"))
    )
  )
)
